# JacdacSingleRgbLed_42.net
KiCad netlist of a schematic drawn in Altium Designer
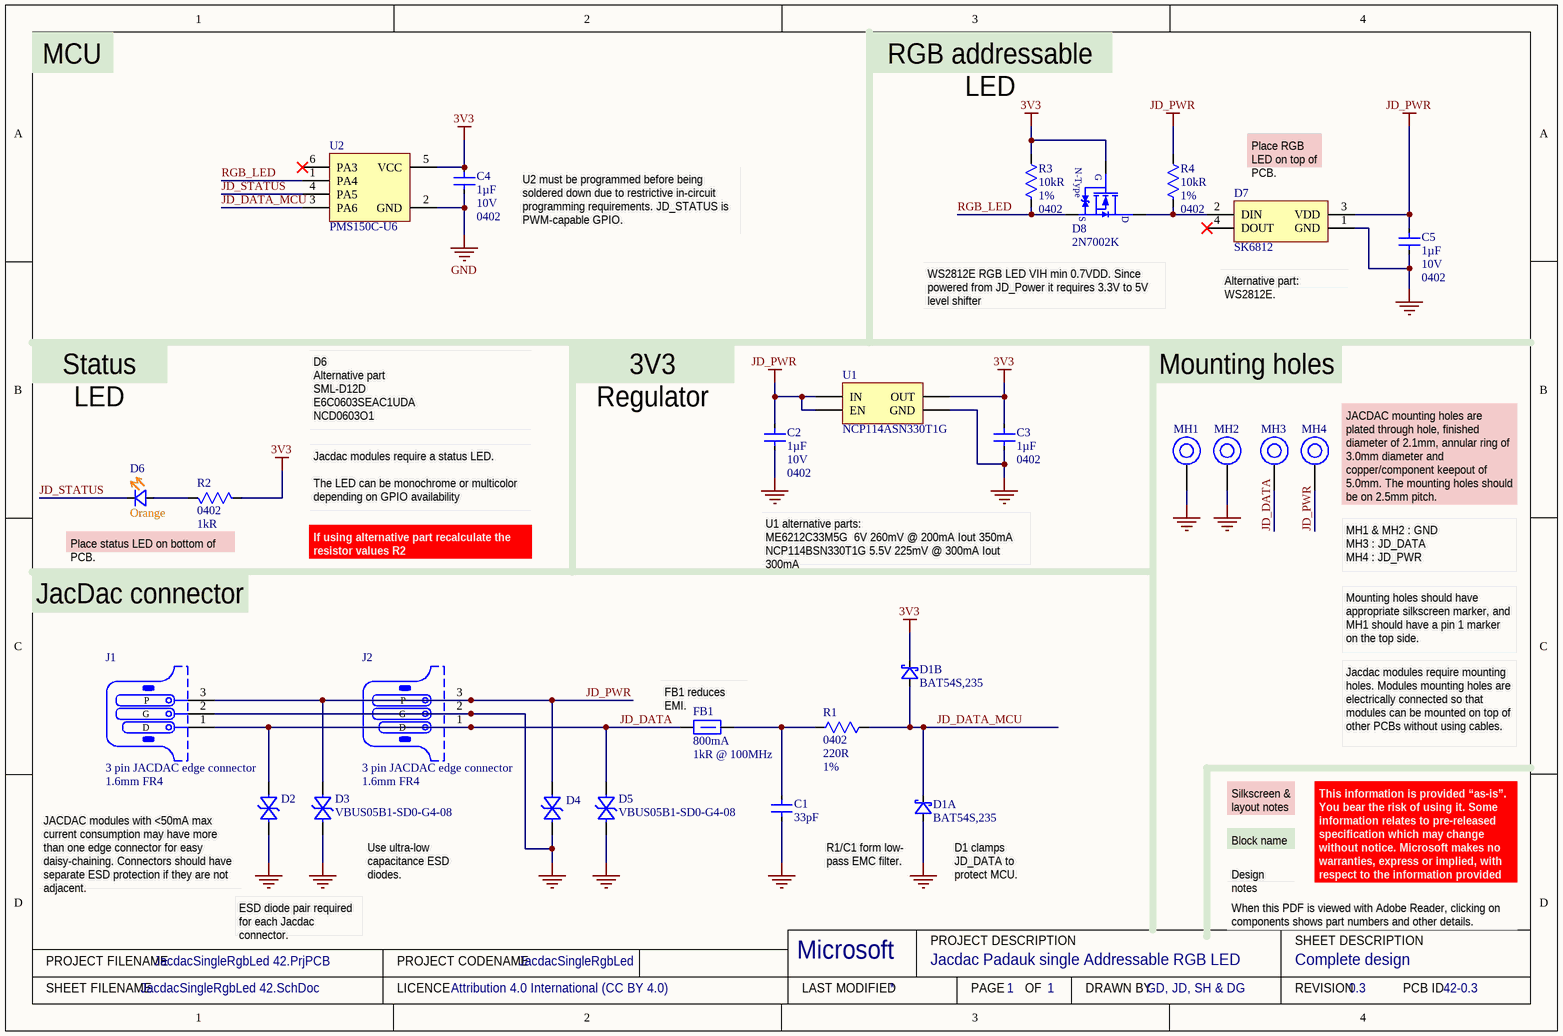
[diagram p0: JacdacSingleRgbLed 42.SchDoc]

(export (version "E")
  (design (tool "Eeschema 10.0.6"))
  (components
    (comp (ref "C1")
      (value "CL05C330JB51PNC")
      (footprint "C0402_0.55MM - without outline")
      (description "CAP CER 33PF 50V NP0 0402")
      (fields
        (field (name "MANUFACTURER") "Samsung")
        (field (name "TOLERANCE") "5%")
        (field (name "CAPACITANCE") "33pF")
        (field (name "CHECKED") "?")
        (field (name "CREATED") "DG")
      )
      (libsource (lib "Samsung") (part "CL05C330JB51PNC"))
    )
    (comp (ref "C2")
      (value "CL05A105KP5NNNC")
      (footprint "C0402_0.55MM - without outline")
      (description "CAP CER 1UF 10V X5R 0402")
      (fields
        (field (name "MANUFACTURER") "Samsung")
        (field (name "TOLERANCE") "10%")
        (field (name "CAPACITANCE") "1µF")
        (field (name "VOLTAGE RATING") "10V")
        (field (name "CASE CODE (IMPERIAL)") "0402")
        (field (name "CREATED") "DG")
        (field (name "CHECKED") "?")
      )
      (libsource (lib "Samsung") (part "CL05A105KP5NNNC"))
    )
    (comp (ref "C3")
      (value "CL05A105KP5NNNC")
      (footprint "C0402_0.55MM - without outline")
      (description "CAP CER 1UF 10V X5R 0402")
      (fields
        (field (name "MANUFACTURER") "Samsung")
        (field (name "TOLERANCE") "10%")
        (field (name "CAPACITANCE") "1µF")
        (field (name "CASE CODE (IMPERIAL)") "0402")
        (field (name "CREATED") "DG")
        (field (name "CHECKED") "?")
      )
      (libsource (lib "Samsung") (part "CL05A105KP5NNNC"))
    )
    (comp (ref "C4")
      (value "CL05A105KP5NNNC")
      (footprint "C0402_0.55MM - without outline")
      (description "CAP CER 1UF 10V X5R 0402")
      (fields
        (field (name "MANUFACTURER") "Samsung")
        (field (name "TOLERANCE") "10%")
        (field (name "CAPACITANCE") "1µF")
        (field (name "VOLTAGE RATING") "10V")
        (field (name "CASE CODE (IMPERIAL)") "0402")
        (field (name "CREATED") "DG")
        (field (name "CHECKED") "?")
      )
      (libsource (lib "Samsung") (part "CL05A105KP5NNNC"))
    )
    (comp (ref "C5")
      (value "CL05A105KP5NNNC")
      (footprint "C0402_0.55MM - without outline")
      (description "CAP CER 1UF 10V X5R 0402")
      (fields
        (field (name "MANUFACTURER") "Samsung")
        (field (name "TOLERANCE") "10%")
        (field (name "CAPACITANCE") "1µF")
        (field (name "VOLTAGE RATING") "10V")
        (field (name "CASE CODE (IMPERIAL)") "0402")
        (field (name "CREATED") "DG")
        (field (name "CHECKED") "?")
      )
      (libsource (lib "Samsung") (part "CL05A105KP5NNNC"))
    )
    (comp (ref "D1")
      (value "BAT54S")
      (footprint "NXP-BAT54S-TO-236AB")
      (description "DIODE ARRAY SCHOTTKY 30V SOT23")
      (fields (field (name "MANUFACTURER") "Nexperia") (field (name "MANUFACTURER PART NUMBER") "BAT54S,235"))
      (libsource (lib "NXP") (part "BAT54S"))
    )
    (comp (ref "D2")
      (value "VBUS05B1-SD0-G4-08")
      (footprint "0201-VBUS05B1-SD0-G4-08 - Without outline")
      (description "TVS DIODE 5.5V 18V CLP0603")
      (fields
        (field (name "MANUFACTURER") "Vishay Semiconductors")
        (field (name "CREATED BY") "D. Gakure")
        (field (name "CHECKED BY") "?")
      )
      (libsource (lib "Vishay") (part "VBUS05B1-SD0-G4-08"))
    )
    (comp (ref "D3")
      (value "VBUS05B1-SD0-G4-08")
      (footprint "0201-VBUS05B1-SD0-G4-08 - Without outline")
      (description "TVS DIODE 5.5V 18V CLP0603")
      (fields
        (field (name "MANUFACTURER") "Vishay Semiconductors")
        (field (name "MANUFACTURER PART NUMBER") "VBUS05B1-SD0-G4-08")
        (field (name "CREATED BY") "D. Gakure")
        (field (name "CHECKED BY") "?")
      )
      (libsource (lib "Vishay") (part "VBUS05B1-SD0-G4-08"))
    )
    (comp (ref "D4")
      (value "VBUS05B1-SD0-G4-08")
      (footprint "0201-VBUS05B1-SD0-G4-08 - Without outline")
      (description "TVS DIODE 5.5V 18V CLP0603")
      (fields
        (field (name "MANUFACTURER") "Vishay Semiconductors")
        (field (name "CREATED BY") "D. Gakure")
        (field (name "CHECKED BY") "?")
      )
      (libsource (lib "Vishay") (part "VBUS05B1-SD0-G4-08"))
    )
    (comp (ref "D5")
      (value "VBUS05B1-SD0-G4-08")
      (footprint "0201-VBUS05B1-SD0-G4-08 - Without outline")
      (description "TVS DIODE 5.5V 18V CLP0603")
      (fields
        (field (name "MANUFACTURER") "Vishay Semiconductors")
        (field (name "MANUFACTURER PART NUMBER") "VBUS05B1-SD0-G4-08")
        (field (name "CREATED BY") "D. Gakure")
        (field (name "CHECKED BY") "?")
      )
      (libsource (lib "Vishay") (part "VBUS05B1-SD0-G4-08"))
    )
    (comp (ref "D6")
      (value "SML-D12D")
      (footprint "Rohm SML-D12 Orange - without outline")
      (description "1.6 x 0.8 x 0.55mm (0603) LED 605nm Orange")
      (fields
        (field (name "MANUFACTURER") "Rohm Semiconductor")
        (field (name "MANUFACTURER PART NUMBER") "SML-D12D8WT86")
        (field (name "COLOUR") "Orange")
      )
      (libsource (lib "Rohm") (part "SML-D12D"))
    )
    (comp (ref "D7")
      (value "SK6812")
      (footprint "SK6812 - without outline")
      (description "WS2812B 5050 RGB LED WITH INTEGRATED DRIVER")
      (fields
        (field (name "MANUFACTURER PART NUMBER") "SK6812")
        (field (name "MANUFACTURER") "Shenzhen LED Color")
      )
      (libsource (lib "Shenzhen LED Color") (part "SK6812"))
    )
    (comp (ref "D8")
      (value "2N7002K")
      (footprint "SOT-23")
      (description "MOSFET Transistor, N Channel, 300 mA, 60 V, 2 ohm, 10 V, 2.5 V")
      (fields
        (field (name "MANUFACTURER") "ON Semiconductor / Fairchild")
        (field (name "VOLTAGE") "60V")
        (field (name "MANUFACTURER PART NUMBER") "2N7002K")
        (field (name "CREATED BY") "D. Gakure")
        (field (name "CHECKED BY") "?")
      )
      (libsource (lib "OnSemiconductor") (part "2N7002K (2)"))
    )
    (comp (ref "FB1")
      (value "TDK MPZ1608S102ATA00")
      (footprint "TDK MPZ1608 0.8mm - without outline")
      (description "0603 1k@100MHz 0.8A chip")
      (fields
        (field (name "TOLERANCE") "25%")
        (field (name "MANUFACTURER") "TDK")
        (field (name "CURRENT RATING") "800mA")
        (field (name "IMPEDANCE") "1kR @ 100MHz")
      )
      (libsource (lib "TDK") (part "TDK MPZ1608S102ATA00"))
    )
    (comp (ref "J1")
      (value "3 pin JACDAC edge connector")
      (footprint "JACDAC_EDGE_CONNECTOR_0.15mm_T&G")
      (description "3 pin JACDAC edge connector 1.27mm pitch")
      (fields
        (field (name "MANUFACTURER PART NUMBER") "JACDAC_EDGE_CONNECTOR")
        (field (name "PCB TYPE") "1.6mm FR4")
        (field (name "CHECKED BY") "?")
        (field (name "CREATED BY") "D. Gakure")
      )
      (libsource (lib "generic-con") (part "JACDAC edge connector"))
    )
    (comp (ref "J2")
      (value "3 pin JACDAC edge connector")
      (footprint "JACDAC_EDGE_CONNECTOR_0.15mm_T&G")
      (description "3 pin JACDAC edge connector 1.27mm pitch")
      (fields
        (field (name "MANUFACTURER PART NUMBER") "JACDAC_EDGE_CONNECTOR")
        (field (name "PCB TYPE") "1.6mm FR4")
        (field (name "CHECKED BY") "?")
        (field (name "CREATED BY") "D. Gakure")
      )
      (libsource (lib "generic-con") (part "JACDAC edge connector"))
    )
    (comp (ref "MH1")
      (value "MH_5.0MMK_3.0MMC_2.1MMD_PTH")
      (footprint "MH_5.0MMK_3.0MMC_2.1MMD_PTH")
      (description "Mounting Hole 5.0mm keepout, 3.0mm annualar ring and 2.1mm Drill PTH")
      (libsource (lib "generic") (part "MH_5.0MMK_3.0MMC_2.1MMD_PTH"))
    )
    (comp (ref "MH2")
      (value "MH_5.0MMK_3.0MMC_2.1MMD_PTH")
      (footprint "MH_5.0MMK_3.0MMC_2.1MMD_PTH")
      (description "Mounting Hole 5.0mm keepout, 3.0mm annualar ring and 2.1mm Drill PTH")
      (libsource (lib "generic") (part "MH_5.0MMK_3.0MMC_2.1MMD_PTH"))
    )
    (comp (ref "MH3")
      (value "MH_5.0MMK_3.0MMC_2.1MMD_PTH")
      (footprint "MH_5.0MMK_3.0MMC_2.1MMD_PTH")
      (description "Mounting Hole 5.0mm keepout, 3.0mm annualar ring and 2.1mm Drill PTH")
      (libsource (lib "generic") (part "MH_5.0MMK_3.0MMC_2.1MMD_PTH"))
    )
    (comp (ref "MH4")
      (value "MH_5.0MMK_3.0MMC_2.1MMD_PTH")
      (footprint "MH_5.0MMK_3.0MMC_2.1MMD_PTH")
      (description "Mounting Hole 5.0mm keepout, 3.0mm annualar ring and 2.1mm Drill PTH")
      (libsource (lib "generic") (part "MH_5.0MMK_3.0MMC_2.1MMD_PTH"))
    )
    (comp (ref "R1")
      (value "RC0402FR-07220RL")
      (footprint "R0402 - Without outline")
      (description "RES SMD 220 OHM 1% 1/16W 0402")
      (fields
        (field (name "MANUFACTURER") "Yageo")
        (field (name "CASE CODE (IMPERIAL)") "0402")
        (field (name "RESISTANCE") "220R")
        (field (name "TOLERANCE") "1%")
        (field (name "CREATED") "D.G")
        (field (name "CHECKED") "?")
      )
      (libsource (lib "Yageo") (part "RC0402FR-07220RL"))
    )
    (comp (ref "R2")
      (value "RC0402FR-071KL")
      (footprint "R0402 - Without outline")
      (description "RES SMD 1K OHM 1% 1/16W 0402")
      (fields
        (field (name "MANUFACTURER") "Yageo")
        (field (name "CASE CODE (IMPERIAL)") "0402")
        (field (name "TOLERANCE") "1%")
        (field (name "RESISTANCE") "1kR")
        (field (name "CREATED") "D.G")
        (field (name "CHECKED") "?")
      )
      (libsource (lib "Yageo") (part "RC0402FR-071KL"))
    )
    (comp (ref "R3")
      (value "10k")
      (footprint "R0402 - Without outline")
      (description "RES SMD 10K OHM 1% 1/16W 0402")
      (fields
        (field (name "MANUFACTURER") "Yageo")
        (field (name "MANUFACTURER PART NUMBER") "RC0402FR-0710KL")
        (field (name "RESISTANCE") "10kR")
        (field (name "TOLERANCE") "1%")
        (field (name "CASE CODE (IMPERIAL)") "0402")
        (field (name "CHECKED") "?")
        (field (name "CREATED") "DG")
      )
      (libsource (lib "Yageo") (part "RC0402FR-0710KL"))
    )
    (comp (ref "R4")
      (value "10k")
      (footprint "R0402 - Without outline")
      (description "RES SMD 10K OHM 1% 1/16W 0402")
      (fields
        (field (name "MANUFACTURER") "Yageo")
        (field (name "MANUFACTURER PART NUMBER") "RC0402FR-0710KL")
        (field (name "RESISTANCE") "10kR")
        (field (name "TOLERANCE") "1%")
        (field (name "CASE CODE (IMPERIAL)") "0402")
        (field (name "CHECKED") "?")
        (field (name "CREATED") "DG")
      )
      (libsource (lib "Yageo") (part "RC0402FR-0710KL"))
    )
    (comp (ref "U1")
      (value "LDO 3.3V/300 mA")
      (footprint "ON_SEMI-SOT23-5")
      (fields
        (field (name "MANUFACTURER") "ON Semiconductor")
        (field (name "MANUFACTURER PART NUMBER") "NCP114ASN330T1G")
        (field (name "CREATED") "DG")
        (field (name "CHECKED") "?")
      )
      (libsource (lib "OnSemiconductor") (part "NCP114ASN330T1G"))
    )
    (comp (ref "U2")
      (value "PMS150C")
      (footprint "SOT23-6")
      (description "8bit OTP Type IO Controller")
      (fields (field (name "MANUFACTURER PART NUMBER") "PMS150C-U6") (field (name "MANUFACTURER") "PADAUK"))
      (libsource (lib "PADAUK") (part "PMS150C"))
    )
  )
  (nets
    (net (code "1") (name "/JD_DATA") (class "Default")
      (node (ref "D2") (pin "1") (pinfunction "K_1") (pintype "passive"))
      (node (ref "D5") (pin "1") (pinfunction "K_1") (pintype "passive"))
      (node (ref "FB1") (pin "1") (pinfunction "1_1") (pintype "passive"))
      (node (ref "J1") (pin "1") (pinfunction "D_1") (pintype "passive"))
      (node (ref "J2") (pin "1") (pinfunction "D_1") (pintype "passive"))
      (node (ref "MH3") (pin "1") (pinfunction "1_1") (pintype "passive"))
    )
    (net (code "2") (name "/JD_DATA_MCU") (class "Default")
      (node (ref "D1") (pin "3") (pinfunction "K_3") (pintype "passive"))
      (node (ref "R1") (pin "1") (pinfunction "1_1") (pintype "passive"))
      (node (ref "U2") (pin "3") (pinfunction "PA6_3") (pintype "passive"))
    )
    (net (code "3") (name "/JD_STATUS") (class "Default")
      (node (ref "D6") (pin "1") (pinfunction "K_1") (pintype "passive"))
      (node (ref "U2") (pin "4") (pinfunction "PA5_4") (pintype "passive"))
    )
    (net (code "4") (name "/RGB_LED") (class "Default")
      (node (ref "D8") (pin "2") (pinfunction "S_2") (pintype "passive"))
      (node (ref "R3") (pin "2") (pinfunction "2_2") (pintype "passive"))
      (node (ref "U2") (pin "1") (pinfunction "PA4_1") (pintype "passive"))
    )
    (net (code "5") (name "3V3") (class "Default")
      (node (ref "C3") (pin "2") (pinfunction "2_2") (pintype "passive"))
      (node (ref "C4") (pin "2") (pinfunction "2_2") (pintype "passive"))
      (node (ref "D1") (pin "2") (pinfunction "K_2") (pintype "passive"))
      (node (ref "D8") (pin "1") (pinfunction "G_1") (pintype "passive"))
      (node (ref "R2") (pin "2") (pinfunction "2_2") (pintype "passive"))
      (node (ref "R3") (pin "1") (pinfunction "1_1") (pintype "passive"))
      (node (ref "U1") (pin "5") (pinfunction "OUT_5") (pintype "passive"))
      (node (ref "U2") (pin "5") (pinfunction "VCC_5") (pintype "passive"))
    )
    (net (code "6") (name "GND") (class "Default")
      (node (ref "C1") (pin "1") (pinfunction "1_1") (pintype "passive"))
      (node (ref "C2") (pin "1") (pinfunction "1_1") (pintype "passive"))
      (node (ref "C3") (pin "1") (pinfunction "1_1") (pintype "passive"))
      (node (ref "C4") (pin "1") (pinfunction "1_1") (pintype "passive"))
      (node (ref "C5") (pin "1") (pinfunction "1_1") (pintype "passive"))
      (node (ref "D1") (pin "1") (pinfunction "A_1") (pintype "passive"))
      (node (ref "D2") (pin "2") (pinfunction "A_2") (pintype "passive"))
      (node (ref "D3") (pin "2") (pinfunction "A_2") (pintype "passive"))
      (node (ref "D4") (pin "2") (pinfunction "A_2") (pintype "passive"))
      (node (ref "D5") (pin "2") (pinfunction "A_2") (pintype "passive"))
      (node (ref "D7") (pin "1") (pinfunction "GND_1") (pintype "passive"))
      (node (ref "J1") (pin "2") (pinfunction "G_2") (pintype "passive"))
      (node (ref "J2") (pin "2") (pinfunction "G_2") (pintype "passive"))
      (node (ref "MH1") (pin "1") (pinfunction "1_1") (pintype "passive"))
      (node (ref "MH2") (pin "1") (pinfunction "1_1") (pintype "passive"))
      (node (ref "U1") (pin "2") (pinfunction "GND_2") (pintype "passive"))
      (node (ref "U2") (pin "2") (pinfunction "GND_2") (pintype "passive"))
    )
    (net (code "7") (name "JD_PWR") (class "Default")
      (node (ref "C2") (pin "2") (pinfunction "2_2") (pintype "passive"))
      (node (ref "C5") (pin "2") (pinfunction "2_2") (pintype "passive"))
      (node (ref "D3") (pin "1") (pinfunction "K_1") (pintype "passive"))
      (node (ref "D4") (pin "1") (pinfunction "K_1") (pintype "passive"))
      (node (ref "D7") (pin "3") (pinfunction "VDD_3") (pintype "passive"))
      (node (ref "J1") (pin "3") (pinfunction "P_3") (pintype "passive"))
      (node (ref "J2") (pin "3") (pinfunction "P_3") (pintype "passive"))
      (node (ref "MH4") (pin "1") (pinfunction "1_1") (pintype "passive"))
      (node (ref "R4") (pin "1") (pinfunction "1_1") (pintype "passive"))
      (node (ref "U1") (pin "1") (pinfunction "IN_1") (pintype "passive"))
      (node (ref "U1") (pin "3") (pinfunction "EN_3") (pintype "passive"))
    )
    (net (code "8") (name "Net-(C1-Pad2)") (class "Default")
      (node (ref "C1") (pin "2") (pinfunction "2_2") (pintype "passive"))
      (node (ref "FB1") (pin "2") (pinfunction "2_2") (pintype "passive"))
      (node (ref "R1") (pin "2") (pinfunction "2_2") (pintype "passive"))
    )
    (net (code "9") (name "Net-(D6-A)") (class "Default")
      (node (ref "D6") (pin "2") (pinfunction "A_2") (pintype "passive"))
      (node (ref "R2") (pin "1") (pinfunction "1_1") (pintype "passive"))
    )
    (net (code "10") (name "Net-(D7-DIN)") (class "Default")
      (node (ref "D7") (pin "2") (pinfunction "DIN_2") (pintype "passive"))
      (node (ref "D8") (pin "3") (pinfunction "D_3") (pintype "passive"))
      (node (ref "R4") (pin "2") (pinfunction "2_2") (pintype "passive"))
    )
    (net (code "11") (name "unconnected-(D7-DOUT-Pad4)") (class "Default")
      (node (ref "D7") (pin "4") (pinfunction "DOUT_4") (pintype "passive+no_connect"))
    )
    (net (code "12") (name "unconnected-(U2-PA3-Pad6)") (class "Default")
      (node (ref "U2") (pin "6") (pinfunction "PA3_6") (pintype "passive+no_connect"))
    )
  )
)
